# sdcard.net
KiCad netlist of a schematic drawn in Altium Designer
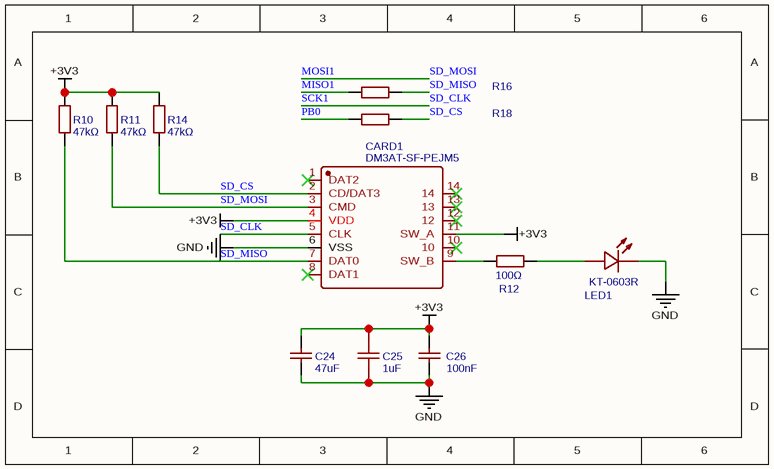
[diagram p0: sdcard.schdoc]

(export (version "E")
  (design (tool "Eeschema 10.0.6"))
  (components
    (comp (ref "C24")
      (value "47uF")
      (fields
        (field (name "MANUFACTURER PART") "CL21A476MQYNNNE")
        (field (name "MANUFACTURER") "SAMSUNG(三星)")
      )
      (libsource (lib "altium-import") (part "root_3_47uF_"))
    )
    (comp (ref "C25")
      (value "1uF")
      (fields
        (field (name "MANUFACTURER") "SAMSUNG(三星)")
        (field (name "MANUFACTURER PART") "CL05A105KA5NQNC")
      )
      (libsource (lib "altium-import") (part "root_3_1uF_"))
    )
    (comp (ref "C26")
      (value "100nF")
      (fields
        (field (name "MANUFACTURER PART") "CL05B104KO5NNNC")
        (field (name "MANUFACTURER") "SAMSUNG(三星)")
      )
      (libsource (lib "altium-import") (part "root_3_100nF_"))
    )
    (comp (ref "CARD1")
      (value "DM3AT-SF-PEJM5")
      (fields (field (name "MANUFACTURER") "HRS(广濑)") (field (name "CONTRIBUTOR") "LCSC"))
      (libsource (lib "altium-import") (part "root_0_DM3AT-SF-PEJM5_"))
    )
    (comp (ref "LED1")
      (value "KT-0603R")
      (fields (field (name "MANUFACTURER") "KENTO"))
      (libsource (lib "altium-import") (part "root_0_KT-0603R_"))
    )
    (comp (ref "R10")
      (value "47kΩ")
      (fields
        (field (name "MANUFACTURER") "UNI-ROYAL(厚声)")
        (field (name "MANUFACTURER PART") "0402WGF4702TCE")
      )
      (libsource (lib "altium-import") (part "root_3_47kΩ_"))
    )
    (comp (ref "R11")
      (value "47kΩ")
      (fields
        (field (name "MANUFACTURER") "UNI-ROYAL(厚声)")
        (field (name "MANUFACTURER PART") "0402WGF4702TCE")
      )
      (libsource (lib "altium-import") (part "root_3_47kΩ_"))
    )
    (comp (ref "R12")
      (value "100Ω")
      (fields
        (field (name "MANUFACTURER") "UNI-ROYAL(厚声)")
        (field (name "MANUFACTURER PART") "0402WGF1000TCE")
      )
      (libsource (lib "altium-import") (part "root_0_100Ω_"))
    )
    (comp (ref "R14")
      (value "47kΩ")
      (fields
        (field (name "MANUFACTURER") "UNI-ROYAL(厚声)")
        (field (name "MANUFACTURER PART") "0402WGF4702TCE")
      )
      (libsource (lib "altium-import") (part "root_3_47kΩ_"))
    )
    (comp (ref "R16")
      (value "22Ω")
      (fields
        (field (name "MANUFACTURER") "UNI-ROYAL(厚声)")
        (field (name "MANUFACTURER PART") "0402WGF220JTCE")
      )
      (libsource (lib "altium-import") (part "root_0_22Ω_"))
    )
    (comp (ref "R18")
      (value "22Ω")
      (fields
        (field (name "MANUFACTURER") "UNI-ROYAL(厚声)")
        (field (name "MANUFACTURER PART") "0402WGF220JTCE")
      )
      (libsource (lib "altium-import") (part "root_0_22Ω_"))
    )
  )
  (nets
    (net (code "1") (name "+3V3") (class "Default")
      (node (ref "C24") (pin "1") (pinfunction "1_1") (pintype "passive"))
      (node (ref "C25") (pin "1") (pinfunction "1_1") (pintype "passive"))
      (node (ref "C26") (pin "2") (pinfunction "2_2") (pintype "passive"))
      (node (ref "CARD1") (pin "11") (pinfunction "SW_A_11") (pintype "passive"))
      (node (ref "CARD1") (pin "4") (pinfunction "VDD_4") (pintype "passive"))
      (node (ref "R10") (pin "1") (pinfunction "1_1") (pintype "passive"))
      (node (ref "R11") (pin "1") (pinfunction "1_1") (pintype "passive"))
      (node (ref "R14") (pin "1") (pinfunction "1_1") (pintype "passive"))
    )
    (net (code "2") (name "/MISO1") (class "Default")
      (node (ref "R16") (pin "1") (pinfunction "1_1") (pintype "passive"))
    )
    (net (code "3") (name "/MOSI1") (class "Default")
      (node (ref "CARD1") (pin "3") (pinfunction "CMD_3") (pintype "passive"))
      (node (ref "R11") (pin "2") (pinfunction "2_2") (pintype "passive"))
    )
    (net (code "4") (name "/PB0") (class "Default")
      (node (ref "R18") (pin "1") (pinfunction "1_1") (pintype "passive"))
    )
    (net (code "5") (name "/SCK1") (class "Default")
      (node (ref "CARD1") (pin "5") (pinfunction "CLK_5") (pintype "passive"))
    )
    (net (code "6") (name "/SD_CS") (class "Default")
      (node (ref "CARD1") (pin "2") (pinfunction "CD/DAT3_2") (pintype "passive"))
      (node (ref "R14") (pin "2") (pinfunction "2_2") (pintype "passive"))
      (node (ref "R18") (pin "2") (pinfunction "2_2") (pintype "passive"))
    )
    (net (code "7") (name "/SD_MISO") (class "Default")
      (node (ref "CARD1") (pin "7") (pinfunction "DAT0_7") (pintype "passive"))
      (node (ref "R10") (pin "2") (pinfunction "2_2") (pintype "passive"))
      (node (ref "R16") (pin "2") (pinfunction "2_2") (pintype "passive"))
    )
    (net (code "8") (name "GND") (class "Default")
      (node (ref "C24") (pin "2") (pinfunction "2_2") (pintype "passive"))
      (node (ref "C25") (pin "2") (pinfunction "2_2") (pintype "passive"))
      (node (ref "C26") (pin "1") (pinfunction "1_1") (pintype "passive"))
      (node (ref "CARD1") (pin "6") (pinfunction "VSS_6") (pintype "passive"))
      (node (ref "LED1") (pin "1") (pinfunction "K_1") (pintype "passive"))
    )
    (net (code "9") (name "Net-(CARD1-SW_B)") (class "Default")
      (node (ref "CARD1") (pin "9") (pinfunction "SW_B_9") (pintype "passive"))
      (node (ref "R12") (pin "1") (pinfunction "1_1") (pintype "passive"))
    )
    (net (code "10") (name "Net-(LED1-A)") (class "Default")
      (node (ref "LED1") (pin "2") (pinfunction "A_2") (pintype "passive"))
      (node (ref "R12") (pin "2") (pinfunction "2_2") (pintype "passive"))
    )
    (net (code "11") (name "unconnected-(CARD1-DAT1-Pad8)") (class "Default")
      (node (ref "CARD1") (pin "8") (pinfunction "DAT1_8") (pintype "passive+no_connect"))
    )
    (net (code "12") (name "unconnected-(CARD1-DAT2-Pad1)") (class "Default")
      (node (ref "CARD1") (pin "1") (pinfunction "DAT2_1") (pintype "passive+no_connect"))
    )
    (net (code "13") (name "unconnected-(CARD1-Pad10)") (class "Default")
      (node (ref "CARD1") (pin "10") (pinfunction "10_10") (pintype "passive+no_connect"))
    )
    (net (code "14") (name "unconnected-(CARD1-Pad12)") (class "Default")
      (node (ref "CARD1") (pin "12") (pinfunction "12_12") (pintype "passive+no_connect"))
    )
    (net (code "15") (name "unconnected-(CARD1-Pad13)") (class "Default")
      (node (ref "CARD1") (pin "13") (pinfunction "13_13") (pintype "passive+no_connect"))
    )
    (net (code "16") (name "unconnected-(CARD1-Pad14)") (class "Default")
      (node (ref "CARD1") (pin "14") (pinfunction "14_14") (pintype "passive+no_connect"))
    )
  )
)
